# lul.net
KiCad netlist of a schematic drawn in EAGLE
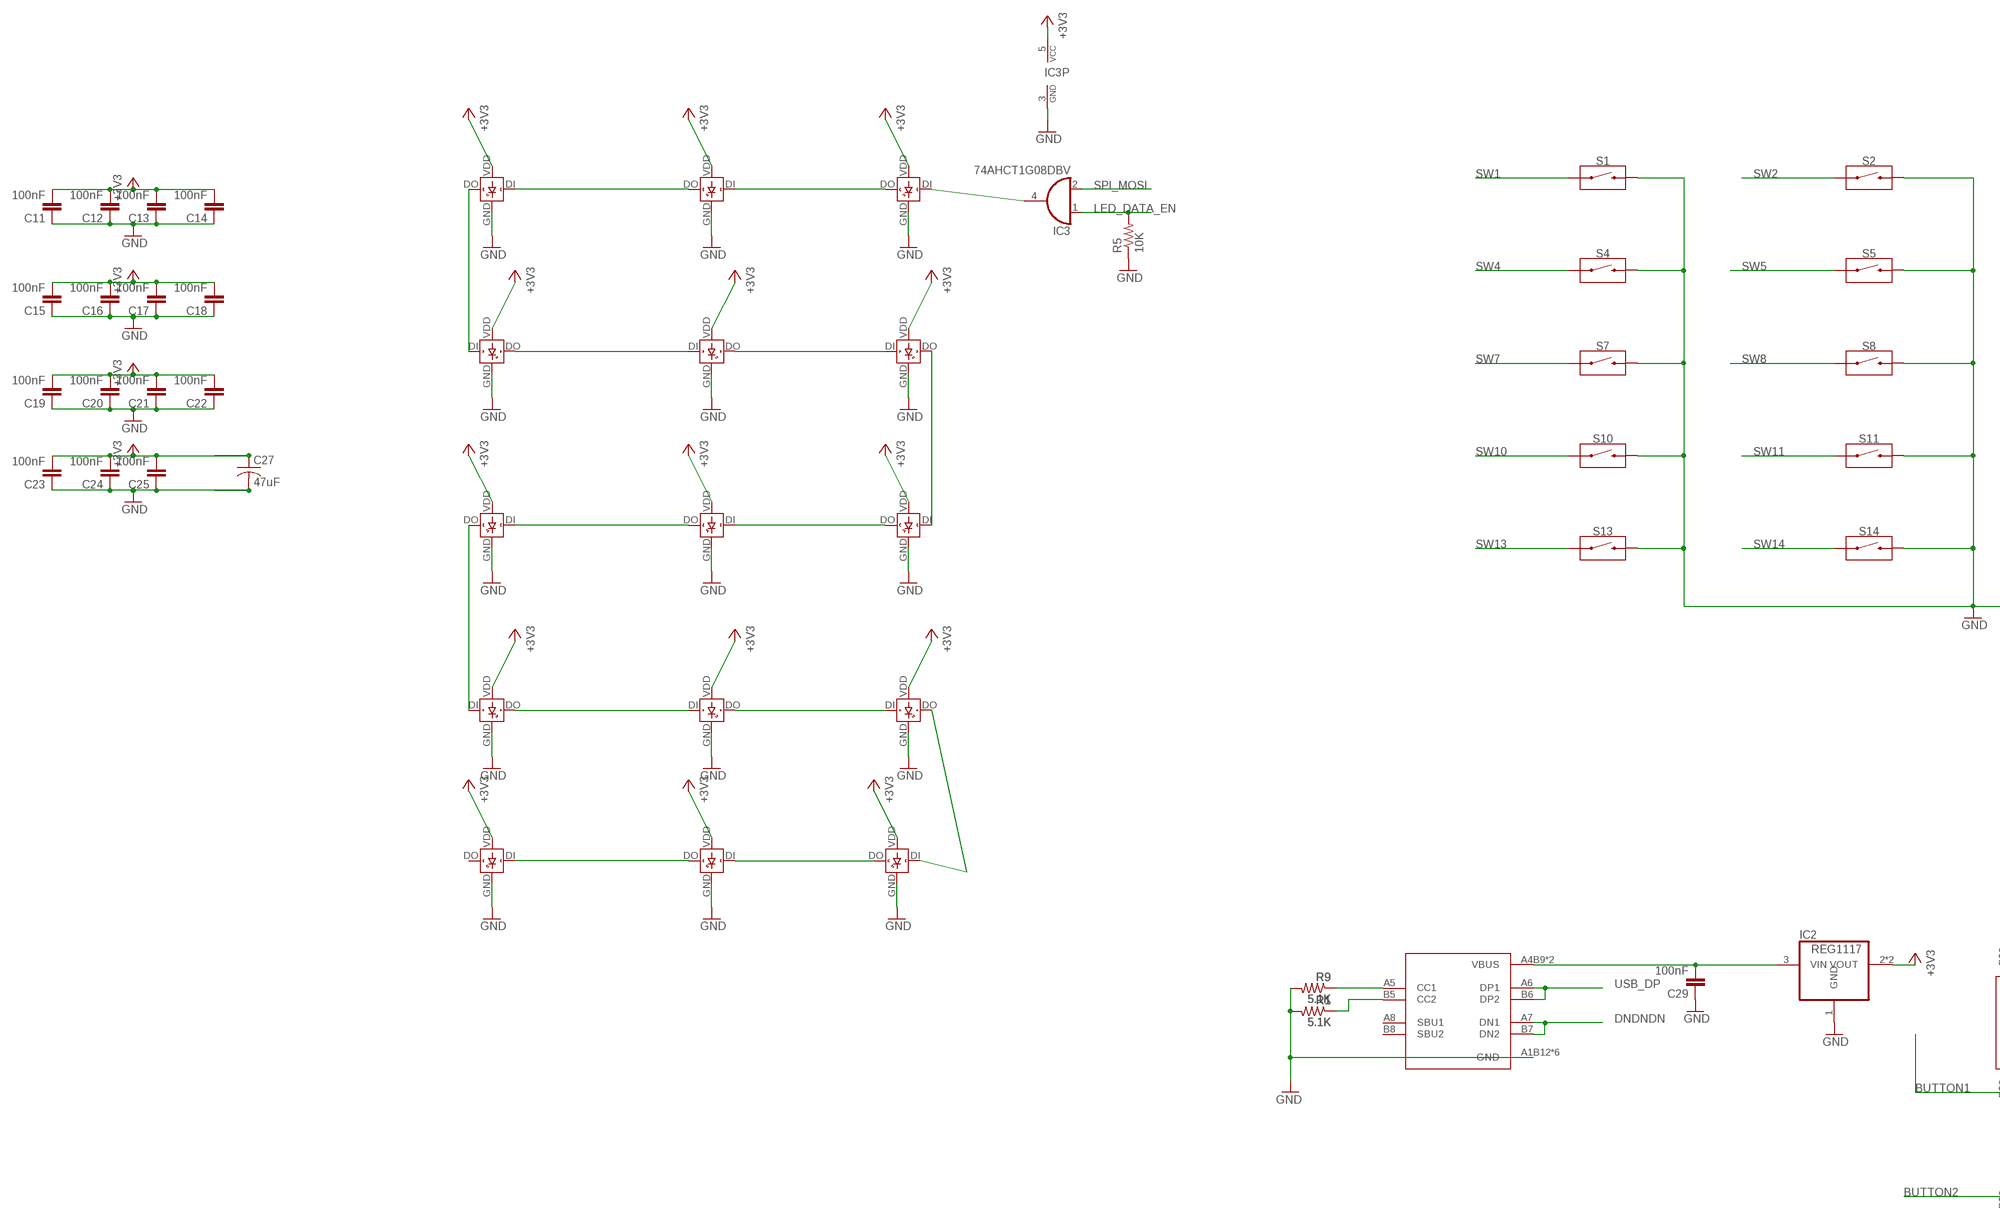
[diagram p0: schematic, sheet 1, part 1 of 2]
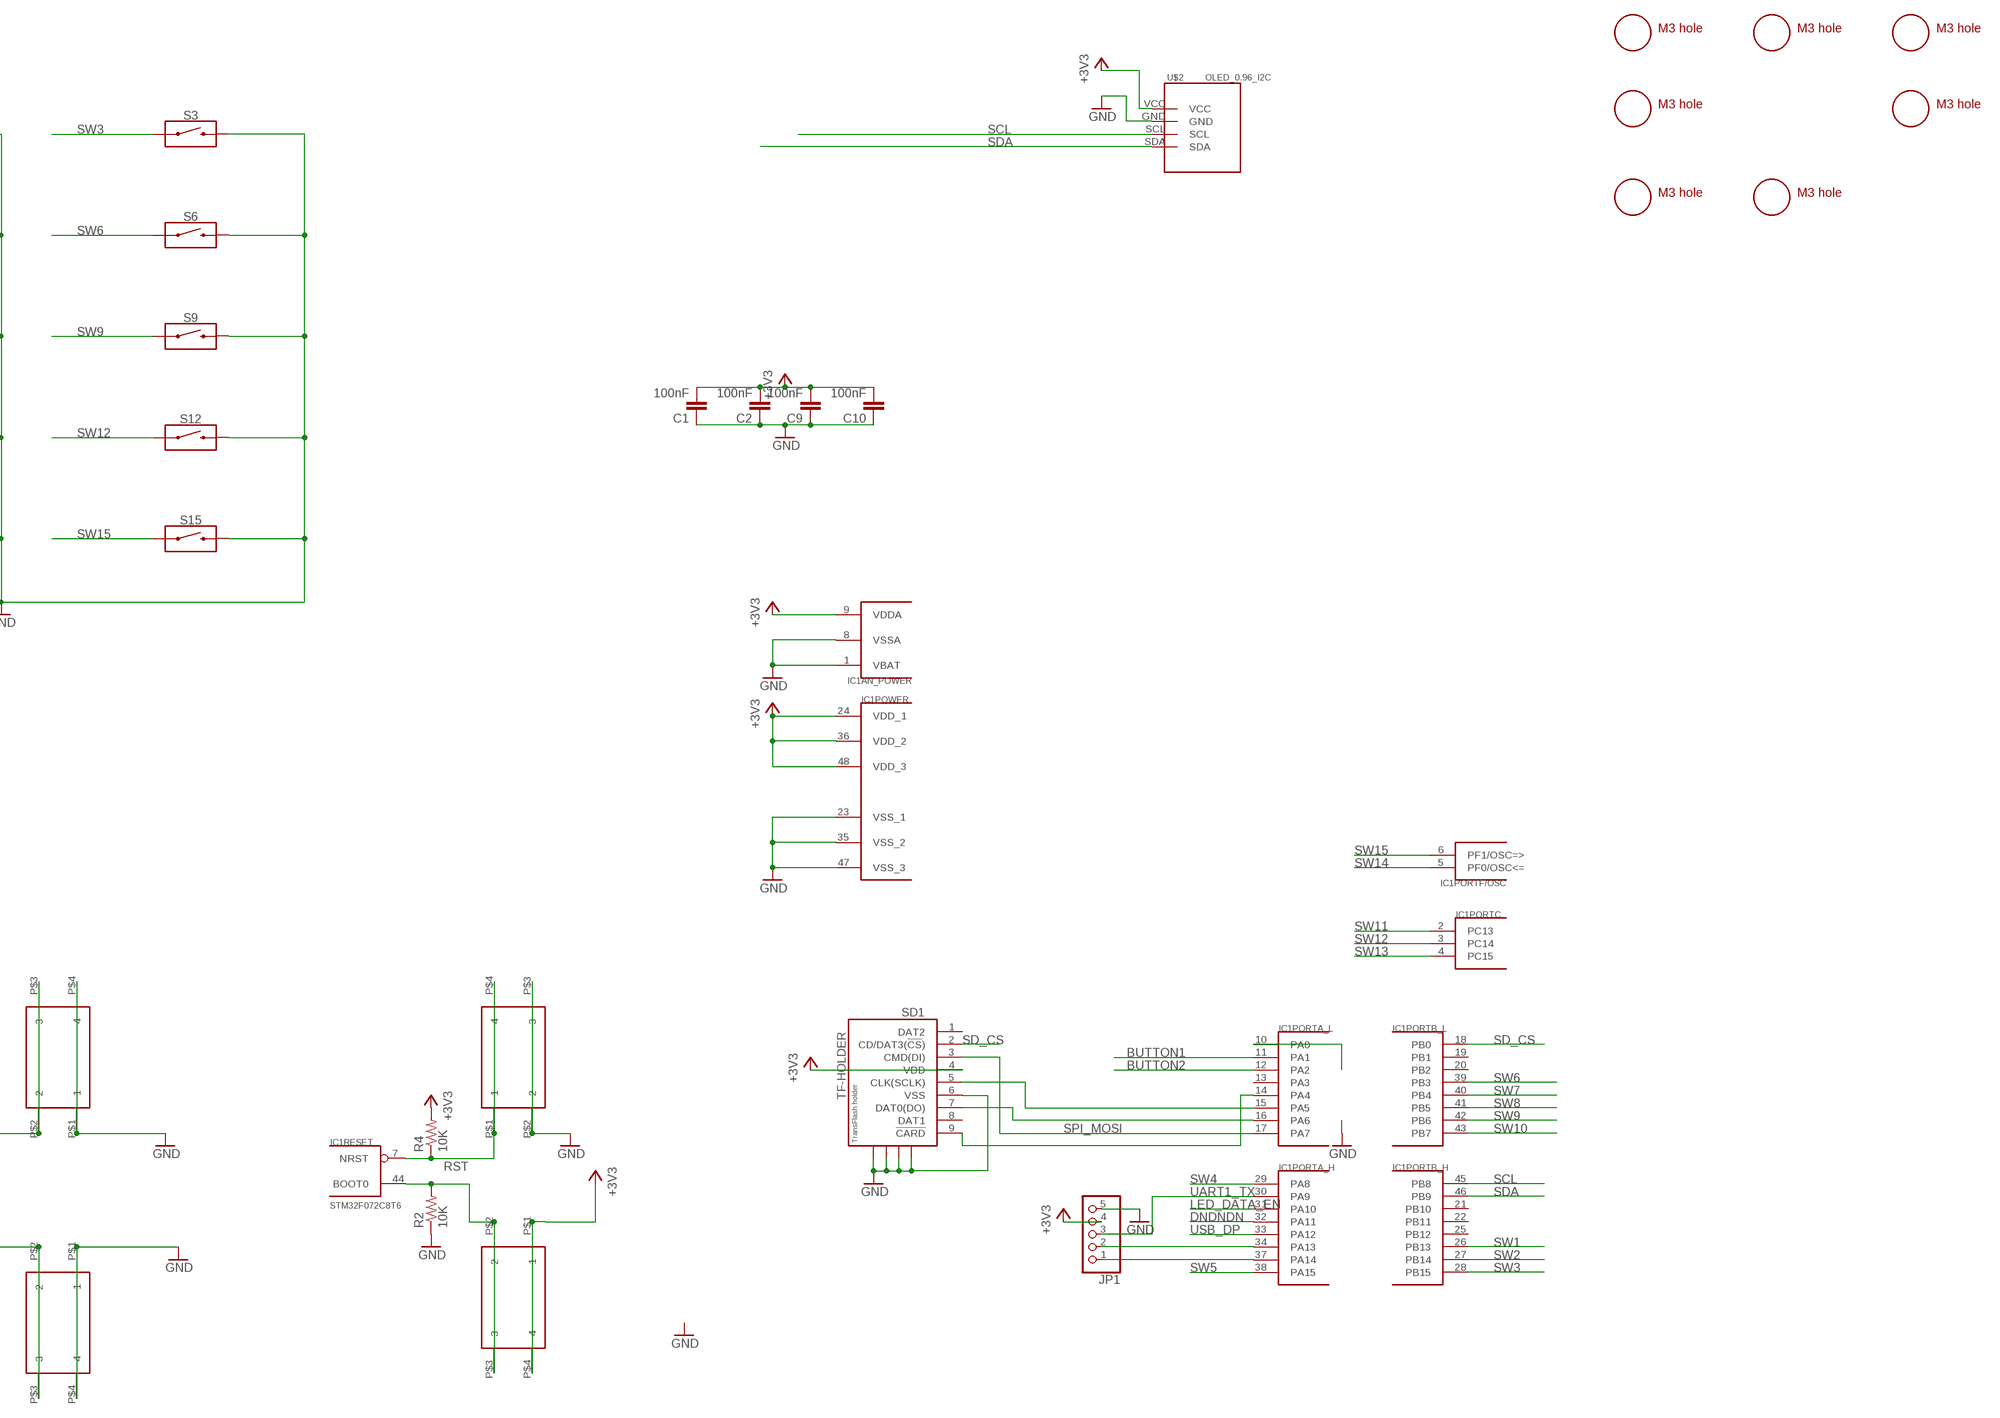
[diagram p1: schematic, sheet 1, part 2 of 2]

(export (version "E")
  (design (tool "Eeschema 10.0.6"))
  (components
    (comp (ref "C1")
      (value "100nF")
      (footprint "eagle-import:0805@1")
      (libsource (lib "eagle-import") (part "CAP0805"))
    )
    (comp (ref "C2")
      (value "100nF")
      (footprint "eagle-import:0805@1")
      (libsource (lib "eagle-import") (part "CAP0805"))
    )
    (comp (ref "C9")
      (value "100nF")
      (footprint "eagle-import:0805@1")
      (libsource (lib "eagle-import") (part "CAP0805"))
    )
    (comp (ref "C10")
      (value "100nF")
      (footprint "eagle-import:0805@1")
      (libsource (lib "eagle-import") (part "CAP0805"))
    )
    (comp (ref "C11")
      (value "100nF")
      (footprint "eagle-import:0805@1")
      (libsource (lib "eagle-import") (part "CAP0805"))
    )
    (comp (ref "C12")
      (value "100nF")
      (footprint "eagle-import:0805@1")
      (libsource (lib "eagle-import") (part "CAP0805"))
    )
    (comp (ref "C13")
      (value "100nF")
      (footprint "eagle-import:0805@1")
      (libsource (lib "eagle-import") (part "CAP0805"))
    )
    (comp (ref "C14")
      (value "100nF")
      (footprint "eagle-import:0805@1")
      (libsource (lib "eagle-import") (part "CAP0805"))
    )
    (comp (ref "C15")
      (value "100nF")
      (footprint "eagle-import:0805@1")
      (libsource (lib "eagle-import") (part "CAP0805"))
    )
    (comp (ref "C16")
      (value "100nF")
      (footprint "eagle-import:0805@1")
      (libsource (lib "eagle-import") (part "CAP0805"))
    )
    (comp (ref "C17")
      (value "100nF")
      (footprint "eagle-import:0805@1")
      (libsource (lib "eagle-import") (part "CAP0805"))
    )
    (comp (ref "C18")
      (value "100nF")
      (footprint "eagle-import:0805@1")
      (libsource (lib "eagle-import") (part "CAP0805"))
    )
    (comp (ref "C19")
      (value "100nF")
      (footprint "eagle-import:0805@1")
      (libsource (lib "eagle-import") (part "CAP0805"))
    )
    (comp (ref "C20")
      (value "100nF")
      (footprint "eagle-import:0805@1")
      (libsource (lib "eagle-import") (part "CAP0805"))
    )
    (comp (ref "C21")
      (value "100nF")
      (footprint "eagle-import:0805@1")
      (libsource (lib "eagle-import") (part "CAP0805"))
    )
    (comp (ref "C22")
      (value "100nF")
      (footprint "eagle-import:0805@1")
      (libsource (lib "eagle-import") (part "CAP0805"))
    )
    (comp (ref "C23")
      (value "100nF")
      (footprint "eagle-import:0805@1")
      (libsource (lib "eagle-import") (part "CAP0805"))
    )
    (comp (ref "C24")
      (value "100nF")
      (footprint "eagle-import:0805@1")
      (libsource (lib "eagle-import") (part "CAP0805"))
    )
    (comp (ref "C25")
      (value "100nF")
      (footprint "eagle-import:0805@1")
      (libsource (lib "eagle-import") (part "CAP0805"))
    )
    (comp (ref "C27")
      (value "47uF")
      (footprint "eagle-import:C1210")
      (libsource (lib "eagle-import") (part "C-USC1210"))
    )
    (comp (ref "C29")
      (value "100nF")
      (footprint "eagle-import:0805@1")
      (libsource (lib "eagle-import") (part "CAP0805"))
    )
    (comp (ref "IC1")
      (value "STM32F072C8T6")
      (footprint "eagle-import:TQFP48")
      (libsource (lib "eagle-import") (part "STM32F072C8T6"))
    )
    (comp (ref "IC2")
      (value "REG1117")
      (footprint "eagle-import:SOT223")
      (libsource (lib "eagle-import") (part "REG1117"))
    )
    (comp (ref "IC3")
      (value "74AHCT1G08DBV")
      (footprint "eagle-import:SOT23-5")
      (libsource (lib "eagle-import") (part "741G08DBVAHCT"))
    )
    (comp (ref "JP1")
      (value "PINHD-1X5")
      (footprint "eagle-import:1X05")
      (libsource (lib "eagle-import") (part "PINHD-1X5"))
    )
    (comp (ref "LED1")
      (value "WS2812B-MINI")
      (footprint "eagle-import:WS2812B-MINI")
      (libsource (lib "eagle-import") (part "WS2812B-MINI"))
    )
    (comp (ref "LED2")
      (value "WS2812B-MINI")
      (footprint "eagle-import:WS2812B-MINI")
      (libsource (lib "eagle-import") (part "WS2812B-MINI"))
    )
    (comp (ref "LED3")
      (value "WS2812B-MINI")
      (footprint "eagle-import:WS2812B-MINI")
      (libsource (lib "eagle-import") (part "WS2812B-MINI"))
    )
    (comp (ref "LED4")
      (value "WS2812B-MINI")
      (footprint "eagle-import:WS2812B-MINI")
      (libsource (lib "eagle-import") (part "WS2812B-MINI"))
    )
    (comp (ref "LED5")
      (value "WS2812B-MINI")
      (footprint "eagle-import:WS2812B-MINI")
      (libsource (lib "eagle-import") (part "WS2812B-MINI"))
    )
    (comp (ref "LED6")
      (value "WS2812B-MINI")
      (footprint "eagle-import:WS2812B-MINI")
      (libsource (lib "eagle-import") (part "WS2812B-MINI"))
    )
    (comp (ref "LED7")
      (value "WS2812B-MINI")
      (footprint "eagle-import:WS2812B-MINI")
      (libsource (lib "eagle-import") (part "WS2812B-MINI"))
    )
    (comp (ref "LED8")
      (value "WS2812B-MINI")
      (footprint "eagle-import:WS2812B-MINI")
      (libsource (lib "eagle-import") (part "WS2812B-MINI"))
    )
    (comp (ref "LED9")
      (value "WS2812B-MINI")
      (footprint "eagle-import:WS2812B-MINI")
      (libsource (lib "eagle-import") (part "WS2812B-MINI"))
    )
    (comp (ref "LED10")
      (value "WS2812B-MINI")
      (footprint "eagle-import:WS2812B-MINI")
      (libsource (lib "eagle-import") (part "WS2812B-MINI"))
    )
    (comp (ref "LED11")
      (value "WS2812B-MINI")
      (footprint "eagle-import:WS2812B-MINI")
      (libsource (lib "eagle-import") (part "WS2812B-MINI"))
    )
    (comp (ref "LED12")
      (value "WS2812B-MINI")
      (footprint "eagle-import:WS2812B-MINI")
      (libsource (lib "eagle-import") (part "WS2812B-MINI"))
    )
    (comp (ref "LED13")
      (value "WS2812B-MINI")
      (footprint "eagle-import:WS2812B-MINI")
      (libsource (lib "eagle-import") (part "WS2812B-MINI"))
    )
    (comp (ref "LED14")
      (value "WS2812B-MINI")
      (footprint "eagle-import:WS2812B-MINI")
      (libsource (lib "eagle-import") (part "WS2812B-MINI"))
    )
    (comp (ref "LED15")
      (value "WS2812B-MINI")
      (footprint "eagle-import:WS2812B-MINI")
      (libsource (lib "eagle-import") (part "WS2812B-MINI"))
    )
    (comp (ref "R1")
      (value "5.1K")
      (footprint "eagle-import:0805")
      (libsource (lib "eagle-import") (part "joyAnalog_RESISTOR0805-RES"))
    )
    (comp (ref "R2")
      (value "10K")
      (footprint "eagle-import:0805")
      (libsource (lib "eagle-import") (part "RESISTOR0805-RES"))
    )
    (comp (ref "R4")
      (value "10K")
      (footprint "eagle-import:0805")
      (libsource (lib "eagle-import") (part "RESISTOR0805-RES"))
    )
    (comp (ref "R5")
      (value "10K")
      (footprint "eagle-import:0805")
      (libsource (lib "eagle-import") (part "RESISTOR0805-RES"))
    )
    (comp (ref "R9")
      (value "5.1K")
      (footprint "eagle-import:0805")
      (libsource (lib "eagle-import") (part "joyAnalog_RESISTOR0805-RES"))
    )
    (comp (ref "S1")
      (value "CHERRY-MX-LED")
      (footprint "eagle-import:CHERRY-MX-LED")
      (libsource (lib "eagle-import") (part "CHERRY-MX-LED"))
    )
    (comp (ref "S2")
      (value "CHERRY-MX-LED")
      (footprint "eagle-import:CHERRY-MX-LED")
      (libsource (lib "eagle-import") (part "CHERRY-MX-LED"))
    )
    (comp (ref "S3")
      (value "CHERRY-MX-LED")
      (footprint "eagle-import:CHERRY-MX-LED")
      (libsource (lib "eagle-import") (part "CHERRY-MX-LED"))
    )
    (comp (ref "S4")
      (value "CHERRY-MX-LED")
      (footprint "eagle-import:CHERRY-MX-LED")
      (libsource (lib "eagle-import") (part "CHERRY-MX-LED"))
    )
    (comp (ref "S5")
      (value "CHERRY-MX-LED")
      (footprint "eagle-import:CHERRY-MX-LED")
      (libsource (lib "eagle-import") (part "CHERRY-MX-LED"))
    )
    (comp (ref "S6")
      (value "CHERRY-MX-LED")
      (footprint "eagle-import:CHERRY-MX-LED")
      (libsource (lib "eagle-import") (part "CHERRY-MX-LED"))
    )
    (comp (ref "S7")
      (value "CHERRY-MX-LED")
      (footprint "eagle-import:CHERRY-MX-LED")
      (libsource (lib "eagle-import") (part "CHERRY-MX-LED"))
    )
    (comp (ref "S8")
      (value "CHERRY-MX-LED")
      (footprint "eagle-import:CHERRY-MX-LED")
      (libsource (lib "eagle-import") (part "CHERRY-MX-LED"))
    )
    (comp (ref "S9")
      (value "CHERRY-MX-LED")
      (footprint "eagle-import:CHERRY-MX-LED")
      (libsource (lib "eagle-import") (part "CHERRY-MX-LED"))
    )
    (comp (ref "S10")
      (value "CHERRY-MX-LED")
      (footprint "eagle-import:CHERRY-MX-LED")
      (libsource (lib "eagle-import") (part "CHERRY-MX-LED"))
    )
    (comp (ref "S11")
      (value "CHERRY-MX-LED")
      (footprint "eagle-import:CHERRY-MX-LED")
      (libsource (lib "eagle-import") (part "CHERRY-MX-LED"))
    )
    (comp (ref "S12")
      (value "CHERRY-MX-LED")
      (footprint "eagle-import:CHERRY-MX-LED")
      (libsource (lib "eagle-import") (part "CHERRY-MX-LED"))
    )
    (comp (ref "S13")
      (value "CHERRY-MX-LED")
      (footprint "eagle-import:CHERRY-MX-LED")
      (libsource (lib "eagle-import") (part "CHERRY-MX-LED"))
    )
    (comp (ref "S14")
      (value "CHERRY-MX-LED")
      (footprint "eagle-import:CHERRY-MX-LED")
      (libsource (lib "eagle-import") (part "CHERRY-MX-LED"))
    )
    (comp (ref "S15")
      (value "CHERRY-MX-LED")
      (footprint "eagle-import:CHERRY-MX-LED")
      (libsource (lib "eagle-import") (part "CHERRY-MX-LED"))
    )
    (comp (ref "SD1")
      (value "TF-HOLDER")
      (footprint "eagle-import:TF-PULL")
      (libsource (lib "eagle-import") (part "TF-HOLDER"))
    )
    (comp (ref "SW1")
      (value "324_SW324_SWITCH_FOOT_HOLE")
      (footprint "eagle-import:342_SWICH_FOOT_HOLE")
      (libsource (lib "eagle-import") (part "324_SW324_SWITCH_FOOT_HOLE"))
    )
    (comp (ref "SW2")
      (value "324_SW324_SWITCH_FOOT_HOLE")
      (footprint "eagle-import:342_SWICH_FOOT_HOLE")
      (libsource (lib "eagle-import") (part "324_SW324_SWITCH_FOOT_HOLE"))
    )
    (comp (ref "SW3")
      (value "324_SW324_SWITCH_FOOT_HOLE")
      (footprint "eagle-import:342_SWICH_FOOT_HOLE")
      (libsource (lib "eagle-import") (part "324_SW324_SWITCH_FOOT_HOLE"))
    )
    (comp (ref "SW4")
      (value "324_SW324_SWITCH_FOOT_HOLE")
      (footprint "eagle-import:342_SWICH_FOOT_HOLE")
      (libsource (lib "eagle-import") (part "324_SW324_SWITCH_FOOT_HOLE"))
    )
    (comp (ref "U$2")
      (value "OLED_0.96_I2C")
      (footprint "eagle-import:OLED_0.96_I2C")
      (libsource (lib "eagle-import") (part "OLED_0.96_I2C"))
    )
    (comp (ref "U$7")
      (value "M3_MOUNTING_HOLE")
      (footprint "eagle-import:M3_MOUNTING_HOLE_PACK")
      (libsource (lib "eagle-import") (part "M3_MOUNTING_HOLE"))
    )
    (comp (ref "U$9")
      (value "M3_MOUNTING_HOLE")
      (footprint "eagle-import:M3_MOUNTING_HOLE_PACK")
      (libsource (lib "eagle-import") (part "M3_MOUNTING_HOLE"))
    )
    (comp (ref "U$10")
      (value "M3_MOUNTING_HOLE")
      (footprint "eagle-import:M3_MOUNTING_HOLE_PACK")
      (libsource (lib "eagle-import") (part "M3_MOUNTING_HOLE"))
    )
    (comp (ref "U$11")
      (value "M3_MOUNTING_HOLE")
      (footprint "eagle-import:M3_MOUNTING_HOLE_PACK")
      (libsource (lib "eagle-import") (part "M3_MOUNTING_HOLE"))
    )
    (comp (ref "U$14")
      (value "M3_MOUNTING_HOLE")
      (footprint "eagle-import:M3_MOUNTING_HOLE_PACK")
      (libsource (lib "eagle-import") (part "M3_MOUNTING_HOLE"))
    )
    (comp (ref "U$15")
      (value "M3_MOUNTING_HOLE")
      (footprint "eagle-import:M3_MOUNTING_HOLE_PACK")
      (libsource (lib "eagle-import") (part "M3_MOUNTING_HOLE"))
    )
    (comp (ref "U$16")
      (value "M3_MOUNTING_HOLE")
      (footprint "eagle-import:M3_MOUNTING_HOLE_PACK")
      (libsource (lib "eagle-import") (part "M3_MOUNTING_HOLE"))
    )
    (comp (ref "U2")
      (value "USBC_16P")
      (footprint "eagle-import:USBC_16P_FOOT")
      (libsource (lib "eagle-import") (part "USBC_16P"))
    )
  )
  (nets
    (net (code "1") (name "+3V3") (class "Default")
      (node (ref "C1") (pin "2") (pinfunction "2_2") (pintype "passive"))
      (node (ref "C10") (pin "2") (pinfunction "2_2") (pintype "passive"))
      (node (ref "C11") (pin "2") (pinfunction "2_2") (pintype "passive"))
      (node (ref "C12") (pin "2") (pinfunction "2_2") (pintype "passive"))
      (node (ref "C13") (pin "2") (pinfunction "2_2") (pintype "passive"))
      (node (ref "C14") (pin "2") (pinfunction "2_2") (pintype "passive"))
      (node (ref "C15") (pin "2") (pinfunction "2_2") (pintype "passive"))
      (node (ref "C16") (pin "2") (pinfunction "2_2") (pintype "passive"))
      (node (ref "C17") (pin "2") (pinfunction "2_2") (pintype "passive"))
      (node (ref "C18") (pin "2") (pinfunction "2_2") (pintype "passive"))
      (node (ref "C19") (pin "2") (pinfunction "2_2") (pintype "passive"))
      (node (ref "C2") (pin "2") (pinfunction "2_2") (pintype "passive"))
      (node (ref "C20") (pin "2") (pinfunction "2_2") (pintype "passive"))
      (node (ref "C21") (pin "2") (pinfunction "2_2") (pintype "passive"))
      (node (ref "C22") (pin "2") (pinfunction "2_2") (pintype "passive"))
      (node (ref "C23") (pin "2") (pinfunction "2_2") (pintype "passive"))
      (node (ref "C24") (pin "2") (pinfunction "2_2") (pintype "passive"))
      (node (ref "C25") (pin "2") (pinfunction "2_2") (pintype "passive"))
      (node (ref "C27") (pin "1") (pinfunction "1_1") (pintype "passive"))
      (node (ref "C9") (pin "2") (pinfunction "2_2") (pintype "passive"))
      (node (ref "IC1") (pin "24") (pinfunction "VDD_1_24") (pintype "power_in"))
      (node (ref "IC1") (pin "36") (pinfunction "VDD_2_36") (pintype "power_in"))
      (node (ref "IC1") (pin "48") (pinfunction "VDD_3_48") (pintype "power_in"))
      (node (ref "IC1") (pin "9") (pinfunction "VDDA_9") (pintype "power_in"))
      (node (ref "IC2") (pin "2") (pinfunction "VOUT_2") (pintype "output"))
      (node (ref "IC2") (pin "4") (pinfunction "VOUT_4") (pintype "output"))
      (node (ref "IC3") (pin "5") (pinfunction "VCC_5") (pintype "power_in"))
      (node (ref "JP1") (pin "4") (pinfunction "4_4") (pintype "passive"))
      (node (ref "LED1") (pin "VDD") (pinfunction "VDD_VDD") (pintype "bidirectional"))
      (node (ref "LED10") (pin "VDD") (pinfunction "VDD_VDD") (pintype "bidirectional"))
      (node (ref "LED11") (pin "VDD") (pinfunction "VDD_VDD") (pintype "bidirectional"))
      (node (ref "LED12") (pin "VDD") (pinfunction "VDD_VDD") (pintype "bidirectional"))
      (node (ref "LED13") (pin "VDD") (pinfunction "VDD_VDD") (pintype "bidirectional"))
      (node (ref "LED14") (pin "VDD") (pinfunction "VDD_VDD") (pintype "bidirectional"))
      (node (ref "LED15") (pin "VDD") (pinfunction "VDD_VDD") (pintype "bidirectional"))
      (node (ref "LED2") (pin "VDD") (pinfunction "VDD_VDD") (pintype "bidirectional"))
      (node (ref "LED3") (pin "VDD") (pinfunction "VDD_VDD") (pintype "bidirectional"))
      (node (ref "LED4") (pin "VDD") (pinfunction "VDD_VDD") (pintype "bidirectional"))
      (node (ref "LED5") (pin "VDD") (pinfunction "VDD_VDD") (pintype "bidirectional"))
      (node (ref "LED6") (pin "VDD") (pinfunction "VDD_VDD") (pintype "bidirectional"))
      (node (ref "LED7") (pin "VDD") (pinfunction "VDD_VDD") (pintype "bidirectional"))
      (node (ref "LED8") (pin "VDD") (pinfunction "VDD_VDD") (pintype "bidirectional"))
      (node (ref "LED9") (pin "VDD") (pinfunction "VDD_VDD") (pintype "bidirectional"))
      (node (ref "R4") (pin "2") (pinfunction "2_2") (pintype "passive"))
      (node (ref "SD1") (pin "4") (pinfunction "VDD_4") (pintype "power_in"))
      (node (ref "SW1") (pin "P$1") (pinfunction "1_P$1") (pintype "bidirectional"))
      (node (ref "SW1") (pin "P$4") (pinfunction "4_P$4") (pintype "bidirectional"))
      (node (ref "U$2") (pin "VCC") (pinfunction "VCC_VCC") (pintype "bidirectional"))
    )
    (net (code "2") (name "/BUTTON1") (class "Default")
      (node (ref "IC1") (pin "11") (pinfunction "PA1_11") (pintype "bidirectional"))
      (node (ref "SW3") (pin "P$2") (pinfunction "2_P$2") (pintype "bidirectional"))
      (node (ref "SW3") (pin "P$3") (pinfunction "3_P$3") (pintype "bidirectional"))
    )
    (net (code "3") (name "/BUTTON2") (class "Default")
      (node (ref "IC1") (pin "12") (pinfunction "PA2_12") (pintype "bidirectional"))
      (node (ref "SW4") (pin "P$2") (pinfunction "2_P$2") (pintype "bidirectional"))
      (node (ref "SW4") (pin "P$3") (pinfunction "3_P$3") (pintype "bidirectional"))
    )
    (net (code "4") (name "/DNDNDN") (class "Default")
      (node (ref "IC1") (pin "32") (pinfunction "PA11_32") (pintype "bidirectional"))
      (node (ref "U2") (pin "A7") (pinfunction "DN1_A7") (pintype "bidirectional"))
      (node (ref "U2") (pin "B7") (pinfunction "DN2_B7") (pintype "bidirectional"))
    )
    (net (code "5") (name "/LED_DATA_EN") (class "Default")
      (node (ref "IC1") (pin "31") (pinfunction "PA10_31") (pintype "bidirectional"))
      (node (ref "IC3") (pin "1") (pinfunction "I0_1") (pintype "input"))
      (node (ref "R5") (pin "2") (pinfunction "2_2") (pintype "passive"))
    )
    (net (code "6") (name "/RST") (class "Default")
      (node (ref "IC1") (pin "7") (pinfunction "NRST_7") (pintype "input"))
      (node (ref "R4") (pin "1") (pinfunction "1_1") (pintype "passive"))
      (node (ref "SW2") (pin "P$1") (pinfunction "1_P$1") (pintype "bidirectional"))
      (node (ref "SW2") (pin "P$4") (pinfunction "4_P$4") (pintype "bidirectional"))
    )
    (net (code "7") (name "/SCL") (class "Default")
      (node (ref "IC1") (pin "45") (pinfunction "PB8_45") (pintype "bidirectional"))
      (node (ref "U$2") (pin "SCL") (pinfunction "SCL_SCL") (pintype "bidirectional"))
    )
    (net (code "8") (name "/SDA") (class "Default")
      (node (ref "IC1") (pin "46") (pinfunction "PB9_46") (pintype "bidirectional"))
      (node (ref "U$2") (pin "SDA") (pinfunction "SDA_SDA") (pintype "bidirectional"))
    )
    (net (code "9") (name "/SD_CS") (class "Default")
      (node (ref "IC1") (pin "18") (pinfunction "PB0_18") (pintype "bidirectional"))
      (node (ref "SD1") (pin "2") (pinfunction "CD/DAT3(~{CS})_2") (pintype "bidirectional"))
    )
    (net (code "10") (name "/SPI_MOSI") (class "Default")
      (node (ref "IC1") (pin "17") (pinfunction "PA7_17") (pintype "bidirectional"))
      (node (ref "IC3") (pin "2") (pinfunction "I1_2") (pintype "input"))
      (node (ref "SD1") (pin "3") (pinfunction "CMD(DI)_3") (pintype "bidirectional"))
    )
    (net (code "11") (name "/SW1") (class "Default")
      (node (ref "IC1") (pin "26") (pinfunction "PB13_26") (pintype "bidirectional"))
      (node (ref "S1") (pin "S1") (pinfunction "S1_S1") (pintype "passive"))
    )
    (net (code "12") (name "/SW2") (class "Default")
      (node (ref "IC1") (pin "27") (pinfunction "PB14_27") (pintype "bidirectional"))
      (node (ref "S2") (pin "S1") (pinfunction "S1_S1") (pintype "passive"))
    )
    (net (code "13") (name "/SW3") (class "Default")
      (node (ref "IC1") (pin "28") (pinfunction "PB15_28") (pintype "bidirectional"))
      (node (ref "S3") (pin "S1") (pinfunction "S1_S1") (pintype "passive"))
    )
    (net (code "14") (name "/SW4") (class "Default")
      (node (ref "IC1") (pin "29") (pinfunction "PA8_29") (pintype "bidirectional"))
      (node (ref "S4") (pin "S1") (pinfunction "S1_S1") (pintype "passive"))
    )
    (net (code "15") (name "/SW5") (class "Default")
      (node (ref "IC1") (pin "38") (pinfunction "PA15_38") (pintype "bidirectional"))
      (node (ref "S5") (pin "S1") (pinfunction "S1_S1") (pintype "passive"))
    )
    (net (code "16") (name "/SW6") (class "Default")
      (node (ref "IC1") (pin "39") (pinfunction "PB3_39") (pintype "bidirectional"))
      (node (ref "S6") (pin "S1") (pinfunction "S1_S1") (pintype "passive"))
    )
    (net (code "17") (name "/SW7") (class "Default")
      (node (ref "IC1") (pin "40") (pinfunction "PB4_40") (pintype "bidirectional"))
      (node (ref "S7") (pin "S1") (pinfunction "S1_S1") (pintype "passive"))
    )
    (net (code "18") (name "/SW8") (class "Default")
      (node (ref "IC1") (pin "41") (pinfunction "PB5_41") (pintype "bidirectional"))
      (node (ref "S8") (pin "S1") (pinfunction "S1_S1") (pintype "passive"))
    )
    (net (code "19") (name "/SW9") (class "Default")
      (node (ref "IC1") (pin "42") (pinfunction "PB6_42") (pintype "bidirectional"))
      (node (ref "S9") (pin "S1") (pinfunction "S1_S1") (pintype "passive"))
    )
    (net (code "20") (name "/SW10") (class "Default")
      (node (ref "IC1") (pin "43") (pinfunction "PB7_43") (pintype "bidirectional"))
      (node (ref "S10") (pin "S1") (pinfunction "S1_S1") (pintype "passive"))
    )
    (net (code "21") (name "/SW11") (class "Default")
      (node (ref "IC1") (pin "2") (pinfunction "PC13_2") (pintype "bidirectional"))
      (node (ref "S11") (pin "S1") (pinfunction "S1_S1") (pintype "passive"))
    )
    (net (code "22") (name "/SW12") (class "Default")
      (node (ref "IC1") (pin "3") (pinfunction "PC14_3") (pintype "bidirectional"))
      (node (ref "S12") (pin "S1") (pinfunction "S1_S1") (pintype "passive"))
    )
    (net (code "23") (name "/SW13") (class "Default")
      (node (ref "IC1") (pin "4") (pinfunction "PC15_4") (pintype "bidirectional"))
      (node (ref "S13") (pin "S1") (pinfunction "S1_S1") (pintype "passive"))
    )
    (net (code "24") (name "/SW14") (class "Default")
      (node (ref "IC1") (pin "5") (pinfunction "PF0/OSC<=_5") (pintype "bidirectional"))
      (node (ref "S14") (pin "S1") (pinfunction "S1_S1") (pintype "passive"))
    )
    (net (code "25") (name "/SW15") (class "Default")
      (node (ref "IC1") (pin "6") (pinfunction "PF1/OSC=>_6") (pintype "bidirectional"))
      (node (ref "S15") (pin "S1") (pinfunction "S1_S1") (pintype "passive"))
    )
    (net (code "26") (name "/UART1_TX") (class "Default")
      (node (ref "IC1") (pin "30") (pinfunction "PA9_30") (pintype "bidirectional"))
      (node (ref "JP1") (pin "3") (pinfunction "3_3") (pintype "passive"))
    )
    (net (code "27") (name "/USB_DP") (class "Default")
      (node (ref "IC1") (pin "33") (pinfunction "PA12_33") (pintype "bidirectional"))
      (node (ref "U2") (pin "A6") (pinfunction "DP1_A6") (pintype "bidirectional"))
      (node (ref "U2") (pin "B6") (pinfunction "DP2_B6") (pintype "bidirectional"))
    )
    (net (code "28") (name "GND") (class "Default")
      (node (ref "C1") (pin "1") (pinfunction "1_1") (pintype "passive"))
      (node (ref "C10") (pin "1") (pinfunction "1_1") (pintype "passive"))
      (node (ref "C11") (pin "1") (pinfunction "1_1") (pintype "passive"))
      (node (ref "C12") (pin "1") (pinfunction "1_1") (pintype "passive"))
      (node (ref "C13") (pin "1") (pinfunction "1_1") (pintype "passive"))
      (node (ref "C14") (pin "1") (pinfunction "1_1") (pintype "passive"))
      (node (ref "C15") (pin "1") (pinfunction "1_1") (pintype "passive"))
      (node (ref "C16") (pin "1") (pinfunction "1_1") (pintype "passive"))
      (node (ref "C17") (pin "1") (pinfunction "1_1") (pintype "passive"))
      (node (ref "C18") (pin "1") (pinfunction "1_1") (pintype "passive"))
      (node (ref "C19") (pin "1") (pinfunction "1_1") (pintype "passive"))
      (node (ref "C2") (pin "1") (pinfunction "1_1") (pintype "passive"))
      (node (ref "C20") (pin "1") (pinfunction "1_1") (pintype "passive"))
      (node (ref "C21") (pin "1") (pinfunction "1_1") (pintype "passive"))
      (node (ref "C22") (pin "1") (pinfunction "1_1") (pintype "passive"))
      (node (ref "C23") (pin "1") (pinfunction "1_1") (pintype "passive"))
      (node (ref "C24") (pin "1") (pinfunction "1_1") (pintype "passive"))
      (node (ref "C25") (pin "1") (pinfunction "1_1") (pintype "passive"))
      (node (ref "C27") (pin "2") (pinfunction "2_2") (pintype "passive"))
      (node (ref "C29") (pin "1") (pinfunction "1_1") (pintype "passive"))
      (node (ref "C9") (pin "1") (pinfunction "1_1") (pintype "passive"))
      (node (ref "IC1") (pin "1") (pinfunction "VBAT_1") (pintype "power_in"))
      (node (ref "IC1") (pin "23") (pinfunction "VSS_1_23") (pintype "power_in"))
      (node (ref "IC1") (pin "35") (pinfunction "VSS_2_35") (pintype "power_in"))
      (node (ref "IC1") (pin "47") (pinfunction "VSS_3_47") (pintype "power_in"))
      (node (ref "IC1") (pin "8") (pinfunction "VSSA_8") (pintype "power_in"))
      (node (ref "IC2") (pin "1") (pinfunction "GND_1") (pintype "power_in"))
      (node (ref "IC3") (pin "3") (pinfunction "GND_3") (pintype "power_in"))
      (node (ref "JP1") (pin "5") (pinfunction "5_5") (pintype "passive"))
      (node (ref "LED1") (pin "GND") (pinfunction "GND_GND") (pintype "bidirectional"))
      (node (ref "LED10") (pin "GND") (pinfunction "GND_GND") (pintype "bidirectional"))
      (node (ref "LED11") (pin "GND") (pinfunction "GND_GND") (pintype "bidirectional"))
      (node (ref "LED12") (pin "GND") (pinfunction "GND_GND") (pintype "bidirectional"))
      (node (ref "LED13") (pin "GND") (pinfunction "GND_GND") (pintype "bidirectional"))
      (node (ref "LED14") (pin "GND") (pinfunction "GND_GND") (pintype "bidirectional"))
      (node (ref "LED15") (pin "GND") (pinfunction "GND_GND") (pintype "bidirectional"))
      (node (ref "LED2") (pin "GND") (pinfunction "GND_GND") (pintype "bidirectional"))
      (node (ref "LED3") (pin "GND") (pinfunction "GND_GND") (pintype "bidirectional"))
      (node (ref "LED4") (pin "GND") (pinfunction "GND_GND") (pintype "bidirectional"))
      (node (ref "LED5") (pin "GND") (pinfunction "GND_GND") (pintype "bidirectional"))
      (node (ref "LED6") (pin "GND") (pinfunction "GND_GND") (pintype "bidirectional"))
      (node (ref "LED7") (pin "GND") (pinfunction "GND_GND") (pintype "bidirectional"))
      (node (ref "LED8") (pin "GND") (pinfunction "GND_GND") (pintype "bidirectional"))
      (node (ref "LED9") (pin "GND") (pinfunction "GND_GND") (pintype "bidirectional"))
      (node (ref "R1") (pin "2") (pinfunction "2_2") (pintype "passive"))
      (node (ref "R2") (pin "1") (pinfunction "1_1") (pintype "passive"))
      (node (ref "R5") (pin "1") (pinfunction "1_1") (pintype "passive"))
      (node (ref "R9") (pin "2") (pinfunction "2_2") (pintype "passive"))
      (node (ref "S1") (pin "S2") (pinfunction "S2_S2") (pintype "passive"))
      (node (ref "S10") (pin "S2") (pinfunction "S2_S2") (pintype "passive"))
      (node (ref "S11") (pin "S2") (pinfunction "S2_S2") (pintype "passive"))
      (node (ref "S12") (pin "S2") (pinfunction "S2_S2") (pintype "passive"))
      (node (ref "S13") (pin "S2") (pinfunction "S2_S2") (pintype "passive"))
      (node (ref "S14") (pin "S2") (pinfunction "S2_S2") (pintype "passive"))
      (node (ref "S15") (pin "S2") (pinfunction "S2_S2") (pintype "passive"))
      (node (ref "S2") (pin "S2") (pinfunction "S2_S2") (pintype "passive"))
      (node (ref "S3") (pin "S2") (pinfunction "S2_S2") (pintype "passive"))
      (node (ref "S4") (pin "S2") (pinfunction "S2_S2") (pintype "passive"))
      (node (ref "S5") (pin "S2") (pinfunction "S2_S2") (pintype "passive"))
      (node (ref "S6") (pin "S2") (pinfunction "S2_S2") (pintype "passive"))
      (node (ref "S7") (pin "S2") (pinfunction "S2_S2") (pintype "passive"))
      (node (ref "S8") (pin "S2") (pinfunction "S2_S2") (pintype "passive"))
      (node (ref "S9") (pin "S2") (pinfunction "S2_S2") (pintype "passive"))
      (node (ref "SD1") (pin "6") (pinfunction "VSS_6") (pintype "power_in"))
      (node (ref "SD1") (pin "S1") (pinfunction "S1_S1") (pintype "passive"))
      (node (ref "SD1") (pin "S2") (pinfunction "S2_S2") (pintype "passive"))
      (node (ref "SD1") (pin "S3") (pinfunction "S3_S3") (pintype "passive"))
      (node (ref "SD1") (pin "S4") (pinfunction "S4_S4") (pintype "passive"))
      (node (ref "SW2") (pin "P$2") (pinfunction "2_P$2") (pintype "bidirectional"))
      (node (ref "SW2") (pin "P$3") (pinfunction "3_P$3") (pintype "bidirectional"))
      (node (ref "SW3") (pin "P$1") (pinfunction "1_P$1") (pintype "bidirectional"))
      (node (ref "SW3") (pin "P$4") (pinfunction "4_P$4") (pintype "bidirectional"))
      (node (ref "SW4") (pin "P$1") (pinfunction "1_P$1") (pintype "bidirectional"))
      (node (ref "SW4") (pin "P$4") (pinfunction "4_P$4") (pintype "bidirectional"))
      (node (ref "U$2") (pin "GND") (pinfunction "GND_GND") (pintype "bidirectional"))
      (node (ref "U2") (pin "A1B12") (pinfunction "GND_A1B12") (pintype "bidirectional"))
      (node (ref "U2") (pin "B11A12") (pinfunction "GND_B11A12") (pintype "bidirectional"))
      (node (ref "U2") (pin "P$13") (pinfunction "GND_P$13") (pintype "bidirectional"))
      (node (ref "U2") (pin "P$14") (pinfunction "GND_P$14") (pintype "bidirectional"))
      (node (ref "U2") (pin "P$15") (pinfunction "GND_P$15") (pintype "bidirectional"))
      (node (ref "U2") (pin "P$16") (pinfunction "GND_P$16") (pintype "bidirectional"))
    )
    (net (code "29") (name "Net-(IC1B-PA13)") (class "Default")
      (node (ref "IC1") (pin "34") (pinfunction "PA13_34") (pintype "bidirectional"))
      (node (ref "JP1") (pin "2") (pinfunction "2_2") (pintype "passive"))
    )
    (net (code "30") (name "Net-(IC1B-PA14)") (class "Default")
      (node (ref "IC1") (pin "37") (pinfunction "PA14_37") (pintype "bidirectional"))
      (node (ref "JP1") (pin "1") (pinfunction "1_1") (pintype "passive"))
    )
    (net (code "31") (name "Net-(IC1C-PA4)") (class "Default")
      (node (ref "IC1") (pin "14") (pinfunction "PA4_14") (pintype "bidirectional"))
      (node (ref "SD1") (pin "9") (pinfunction "~{CARD}_9") (pintype "passive"))
    )
    (net (code "32") (name "Net-(IC1C-PA5)") (class "Default")
      (node (ref "IC1") (pin "15") (pinfunction "PA5_15") (pintype "bidirectional"))
      (node (ref "SD1") (pin "5") (pinfunction "CLK(SCLK)_5") (pintype "input"))
    )
    (net (code "33") (name "Net-(IC1C-PA6)") (class "Default")
      (node (ref "IC1") (pin "16") (pinfunction "PA6_16") (pintype "bidirectional"))
      (node (ref "SD1") (pin "7") (pinfunction "DAT0(DO)_7") (pintype "bidirectional"))
    )
    (net (code "34") (name "Net-(IC1I-BOOT0)") (class "Default")
      (node (ref "IC1") (pin "44") (pinfunction "BOOT0_44") (pintype "input"))
      (node (ref "R2") (pin "2") (pinfunction "2_2") (pintype "passive"))
      (node (ref "SW1") (pin "P$2") (pinfunction "2_P$2") (pintype "bidirectional"))
      (node (ref "SW1") (pin "P$3") (pinfunction "3_P$3") (pintype "bidirectional"))
    )
    (net (code "35") (name "Net-(IC2-VIN)") (class "Default")
      (node (ref "C29") (pin "2") (pinfunction "2_2") (pintype "passive"))
      (node (ref "IC2") (pin "3") (pinfunction "VIN_3") (pintype "input"))
      (node (ref "U2") (pin "A4B9") (pinfunction "VBUS_A4B9") (pintype "bidirectional"))
      (node (ref "U2") (pin "B4A9") (pinfunction "VBUS_B4A9") (pintype "bidirectional"))
    )
    (net (code "36") (name "Net-(IC3A-O)") (class "Default")
      (node (ref "IC3") (pin "4") (pinfunction "O_4") (pintype "output"))
      (node (ref "LED3") (pin "DI") (pinfunction "DIN_DI") (pintype "input"))
    )
    (net (code "37") (name "Net-(LED1-DIN)") (class "Default")
      (node (ref "LED1") (pin "DI") (pinfunction "DIN_DI") (pintype "input"))
      (node (ref "LED2") (pin "DO") (pinfunction "DOUT_DO") (pintype "output"))
    )
    (net (code "38") (name "Net-(LED1-DOUT)") (class "Default")
      (node (ref "LED1") (pin "DO") (pinfunction "DOUT_DO") (pintype "output"))
      (node (ref "LED4") (pin "DI") (pinfunction "DIN_DI") (pintype "input"))
    )
    (net (code "39") (name "Net-(LED2-DIN)") (class "Default")
      (node (ref "LED2") (pin "DI") (pinfunction "DIN_DI") (pintype "input"))
      (node (ref "LED3") (pin "DO") (pinfunction "DOUT_DO") (pintype "output"))
    )
    (net (code "40") (name "Net-(LED4-DOUT)") (class "Default")
      (node (ref "LED4") (pin "DO") (pinfunction "DOUT_DO") (pintype "output"))
      (node (ref "LED5") (pin "DI") (pinfunction "DIN_DI") (pintype "input"))
    )
    (net (code "41") (name "Net-(LED5-DOUT)") (class "Default")
      (node (ref "LED5") (pin "DO") (pinfunction "DOUT_DO") (pintype "output"))
      (node (ref "LED6") (pin "DI") (pinfunction "DIN_DI") (pintype "input"))
    )
    (net (code "42") (name "Net-(LED6-DOUT)") (class "Default")
      (node (ref "LED6") (pin "DO") (pinfunction "DOUT_DO") (pintype "output"))
      (node (ref "LED9") (pin "DI") (pinfunction "DIN_DI") (pintype "input"))
    )
    (net (code "43") (name "Net-(LED7-DIN)") (class "Default")
      (node (ref "LED7") (pin "DI") (pinfunction "DIN_DI") (pintype "input"))
      (node (ref "LED8") (pin "DO") (pinfunction "DOUT_DO") (pintype "output"))
    )
    (net (code "44") (name "Net-(LED8-DIN)") (class "Default")
      (node (ref "LED8") (pin "DI") (pinfunction "DIN_DI") (pintype "input"))
      (node (ref "LED9") (pin "DO") (pinfunction "DOUT_DO") (pintype "output"))
    )
    (net (code "45") (name "Net-(LED10-DIN)") (class "Default")
      (node (ref "LED10") (pin "DI") (pinfunction "DIN_DI") (pintype "input"))
      (node (ref "LED7") (pin "DO") (pinfunction "DOUT_DO") (pintype "output"))
    )
    (net (code "46") (name "Net-(LED10-DOUT)") (class "Default")
      (node (ref "LED10") (pin "DO") (pinfunction "DOUT_DO") (pintype "output"))
      (node (ref "LED11") (pin "DI") (pinfunction "DIN_DI") (pintype "input"))
    )
    (net (code "47") (name "Net-(LED11-DOUT)") (class "Default")
      (node (ref "LED11") (pin "DO") (pinfunction "DOUT_DO") (pintype "output"))
      (node (ref "LED12") (pin "DI") (pinfunction "DIN_DI") (pintype "input"))
    )
    (net (code "48") (name "Net-(LED12-DOUT)") (class "Default")
      (node (ref "LED12") (pin "DO") (pinfunction "DOUT_DO") (pintype "output"))
      (node (ref "LED15") (pin "DI") (pinfunction "DIN_DI") (pintype "input"))
    )
    (net (code "49") (name "Net-(LED13-DIN)") (class "Default")
      (node (ref "LED13") (pin "DI") (pinfunction "DIN_DI") (pintype "input"))
      (node (ref "LED14") (pin "DO") (pinfunction "DOUT_DO") (pintype "output"))
    )
    (net (code "50") (name "Net-(LED14-DIN)") (class "Default")
      (node (ref "LED14") (pin "DI") (pinfunction "DIN_DI") (pintype "input"))
      (node (ref "LED15") (pin "DO") (pinfunction "DOUT_DO") (pintype "output"))
    )
    (net (code "51") (name "Net-(U2-CC1)") (class "Default")
      (node (ref "R9") (pin "1") (pinfunction "1_1") (pintype "passive"))
      (node (ref "U2") (pin "A5") (pinfunction "CC1_A5") (pintype "bidirectional"))
    )
    (net (code "52") (name "Net-(U2-CC2)") (class "Default")
      (node (ref "R1") (pin "1") (pinfunction "1_1") (pintype "passive"))
      (node (ref "U2") (pin "B5") (pinfunction "CC2_B5") (pintype "bidirectional"))
    )
    (net (code "53") (name "unconnected-(IC1C-PA0-Pad10)") (class "Default")
      (node (ref "IC1") (pin "10") (pinfunction "PA0_10") (pintype "bidirectional"))
    )
    (net (code "54") (name "unconnected-(IC1C-PA3-Pad13)") (class "Default")
      (node (ref "IC1") (pin "13") (pinfunction "PA3_13") (pintype "bidirectional"))
    )
    (net (code "55") (name "unconnected-(IC1D-PB10-Pad21)") (class "Default")
      (node (ref "IC1") (pin "21") (pinfunction "PB10_21") (pintype "bidirectional"))
    )
    (net (code "56") (name "unconnected-(IC1D-PB11-Pad22)") (class "Default")
      (node (ref "IC1") (pin "22") (pinfunction "PB11_22") (pintype "bidirectional"))
    )
    (net (code "57") (name "unconnected-(IC1D-PB12-Pad25)") (class "Default")
      (node (ref "IC1") (pin "25") (pinfunction "PB12_25") (pintype "bidirectional"))
    )
    (net (code "58") (name "unconnected-(IC1E-PB1-Pad19)") (class "Default")
      (node (ref "IC1") (pin "19") (pinfunction "PB1_19") (pintype "bidirectional"))
    )
    (net (code "59") (name "unconnected-(IC1E-PB2-Pad20)") (class "Default")
      (node (ref "IC1") (pin "20") (pinfunction "PB2_20") (pintype "bidirectional"))
    )
    (net (code "60") (name "unconnected-(LED13-DOUT-PadDO)") (class "Default")
      (node (ref "LED13") (pin "DO") (pinfunction "DOUT_DO") (pintype "output"))
    )
    (net (code "61") (name "unconnected-(SD1-DAT1-Pad8)") (class "Default")
      (node (ref "SD1") (pin "8") (pinfunction "DAT1_8") (pintype "bidirectional"))
    )
    (net (code "62") (name "unconnected-(SD1-DAT2-Pad1)") (class "Default")
      (node (ref "SD1") (pin "1") (pinfunction "DAT2_1") (pintype "bidirectional"))
    )
    (net (code "63") (name "unconnected-(U2-SBU1-PadA8)") (class "Default")
      (node (ref "U2") (pin "A8") (pinfunction "SBU1_A8") (pintype "bidirectional"))
    )
    (net (code "64") (name "unconnected-(U2-SBU2-PadB8)") (class "Default")
      (node (ref "U2") (pin "B8") (pinfunction "SBU2_B8") (pintype "bidirectional"))
    )
  )
)
